# Optokoppleradapter_Spannungsmessung_V1_2.net
KiCad netlist of a schematic drawn in Altium Designer
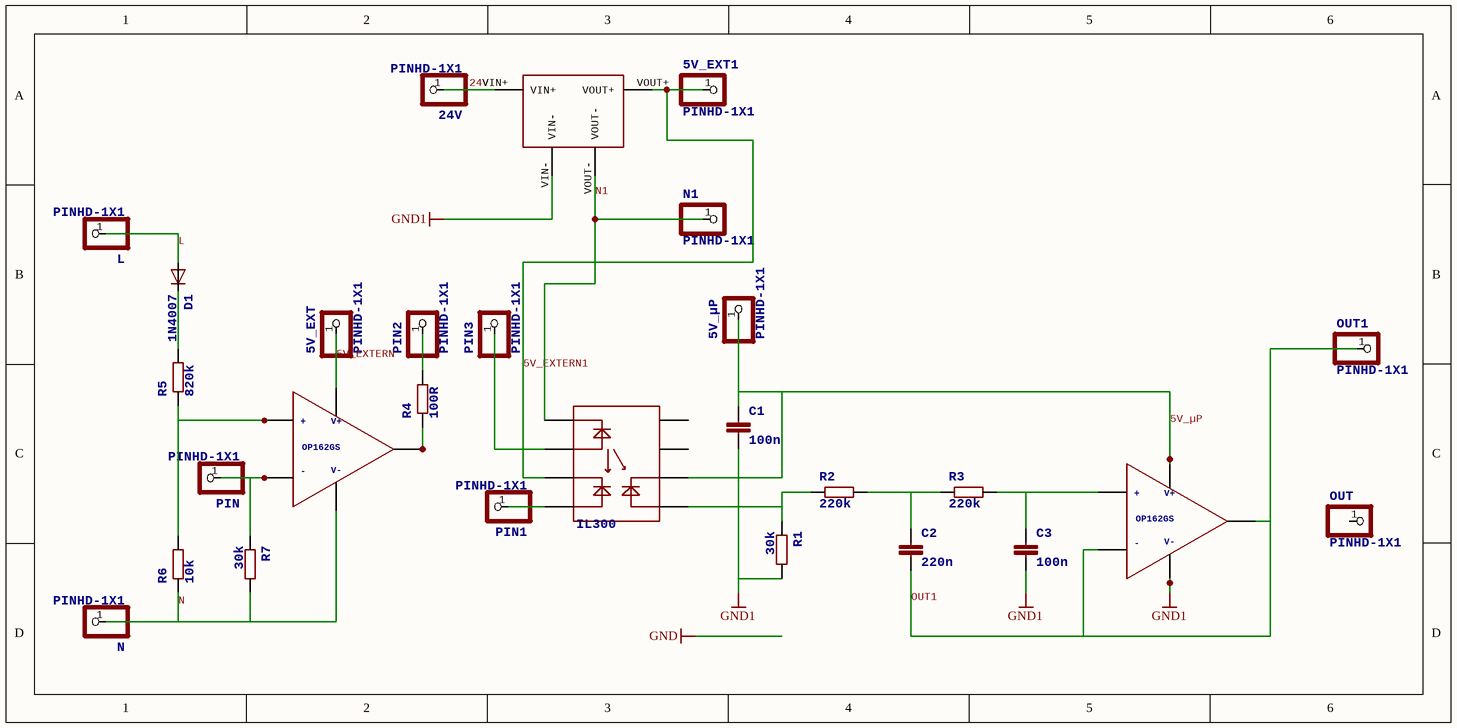
[diagram p0: Optokoppleradapter_Spannungsmessung_V1_2.SchDoc]

(export (version "E")
  (design (tool "Eeschema 10.0.6"))
  (components
    (comp (ref "5V_EXT")
      (value "PINHD-1X1")
      (footprint "1X01")
      (description "<b>PIN HEADER</b>")
      (libsource (lib "pinhead") (part "PINHD-1X1"))
    )
    (comp (ref "5V_EXT1")
      (value "PINHD-1X1")
      (footprint "1X01")
      (description "<b>PIN HEADER</b>")
      (libsource (lib "pinhead") (part "PINHD-1X1"))
    )
    (comp (ref "5V_µP")
      (value "PINHD-1X1")
      (footprint "1X01")
      (description "<b>PIN HEADER</b>")
      (libsource (lib "pinhead") (part "PINHD-1X1"))
    )
    (comp (ref "24V")
      (value "PINHD-1X1")
      (footprint "1X01")
      (description "<b>PIN HEADER</b>")
      (libsource (lib "pinhead") (part "PINHD-1X1"))
    )
    (comp (ref "C1")
      (value "100n")
      (footprint "C0805")
      (description "<B>CAPACITOR</B>, European symbol")
      (libsource (lib "resistor") (part "C-EUC0805"))
    )
    (comp (ref "C2")
      (value "220n")
      (footprint "C0805")
      (description "<B>CAPACITOR</B>, European symbol")
      (libsource (lib "resistor") (part "C-EUC0805"))
    )
    (comp (ref "C3")
      (value "100n")
      (footprint "C0805")
      (description "<B>CAPACITOR</B>, European symbol")
      (libsource (lib "resistor") (part "C-EUC0805"))
    )
    (comp (ref "D1")
      (value "1N4007")
      (footprint "DO35-7")
      (description "<B>DIODE</B><p>\nhigh speed (Philips)")
      (libsource (lib "diode") (part "1N4148DO35-7"))
    )
    (comp (ref "L")
      (value "PINHD-1X1")
      (footprint "1X01")
      (description "<b>PIN HEADER</b>")
      (libsource (lib "pinhead") (part "PINHD-1X1"))
    )
    (comp (ref "N")
      (value "PINHD-1X1")
      (footprint "1X01")
      (description "<b>PIN HEADER</b>")
      (libsource (lib "pinhead") (part "PINHD-1X1"))
    )
    (comp (ref "N1")
      (value "PINHD-1X1")
      (footprint "1X01")
      (description "<b>PIN HEADER</b>")
      (libsource (lib "pinhead") (part "PINHD-1X1"))
    )
    (comp (ref "OUT")
      (value "PINHD-1X1")
      (footprint "1X01")
      (description "<b>PIN HEADER</b>")
      (libsource (lib "pinhead") (part "PINHD-1X1"))
    )
    (comp (ref "OUT1")
      (value "PINHD-1X1")
      (footprint "1X01")
      (description "<b>PIN HEADER</b>")
      (libsource (lib "pinhead") (part "PINHD-1X1"))
    )
    (comp (ref "PIN")
      (value "PINHD-1X1")
      (footprint "1X01")
      (description "<b>PIN HEADER</b>")
      (libsource (lib "pinhead") (part "PINHD-1X1"))
    )
    (comp (ref "PIN1")
      (value "PINHD-1X1")
      (footprint "1X01")
      (description "<b>PIN HEADER</b>")
      (libsource (lib "pinhead") (part "PINHD-1X1"))
    )
    (comp (ref "PIN2")
      (value "PINHD-1X1")
      (footprint "1X01")
      (description "<b>PIN HEADER</b>")
      (libsource (lib "pinhead") (part "PINHD-1X1"))
    )
    (comp (ref "PIN3")
      (value "PINHD-1X1")
      (footprint "1X01")
      (description "<b>PIN HEADER</b>")
      (libsource (lib "pinhead") (part "PINHD-1X1"))
    )
    (comp (ref "R1")
      (value "30k")
      (footprint "R0805")
      (description "<B>RESISTOR</B>, European symbol")
      (libsource (lib "resistor") (part "R-EU_R0805"))
    )
    (comp (ref "R2")
      (value "220k")
      (footprint "R0805")
      (description "<B>RESISTOR</B>, European symbol")
      (libsource (lib "resistor") (part "R-EU_R0805"))
    )
    (comp (ref "R3")
      (value "220k")
      (footprint "R0805")
      (description "<B>RESISTOR</B>, European symbol")
      (libsource (lib "resistor") (part "R-EU_R0805"))
    )
    (comp (ref "R4")
      (value "100R")
      (footprint "R0805")
      (description "<B>RESISTOR</B>, European symbol")
      (libsource (lib "resistor") (part "R-EU_R0805"))
    )
    (comp (ref "R5")
      (value "820k")
      (footprint "0207/7")
      (description "<B>RESISTOR</B>, European symbol")
      (libsource (lib "resistor") (part "R-EU_0207/7"))
    )
    (comp (ref "R6")
      (value "10k")
      (footprint "0207/7")
      (description "<B>RESISTOR</B>, European symbol")
      (libsource (lib "resistor") (part "R-EU_0207/7"))
    )
    (comp (ref "R7")
      (value "30k")
      (footprint "0207/7")
      (description "<B>RESISTOR</B>, European symbol")
      (libsource (lib "resistor") (part "R-EU_0207/7"))
    )
    (comp (ref "U$1")
      (value "IL300")
      (footprint "DIP8")
      (fields (field (name "IL300") "IL300"))
      (libsource (lib "ADS") (part "IL300"))
    )
    (comp (ref "U$2")
      (value "OP162GS")
      (footprint "SOIC_N")
      (fields
        (field (name "+") "+")
        (field (name "-") "-")
        (field (name "OP162GS") "OP162GS")
        (field (name "V+") "V+")
        (field (name "V-") "V-")
      )
      (libsource (lib "ADS") (part "OP162GS"))
    )
    (comp (ref "U$3")
      (value "OP162GS")
      (footprint "SOIC_N")
      (fields
        (field (name "+") "+")
        (field (name "-") "-")
        (field (name "OP162GS") "OP162GS")
        (field (name "V+") "V+")
        (field (name "V-") "V-")
      )
      (libsource (lib "ADS") (part "OP162GS"))
    )
    (comp (ref "U$4")
      (value "RECOM_RO-2405S")
      (footprint "4PIN_SIP")
      (libsource (lib "ADS") (part "RECOM_RO-2405S"))
    )
  )
  (nets
    (net (code "1") (name "/5V_EXTERN") (class "Default")
      (node (ref "5V_EXT") (pin "1") (pinfunction "1_1") (pintype "passive"))
      (node (ref "U$2") (pin "P$7") (pinfunction "V+_P$7") (pintype "passive"))
    )
    (net (code "2") (name "/5V_EXTERN1") (class "Default")
      (node (ref "5V_EXT1") (pin "1") (pinfunction "1_1") (pintype "passive"))
      (node (ref "U$1") (pin "P$3") (pinfunction "P$3_P$3") (pintype "passive"))
      (node (ref "U$4") (pin "VOUT+") (pinfunction "VOUT+_VOUT+") (pintype "passive"))
    )
    (net (code "3") (name "/5V_µP") (class "Default")
      (node (ref "5V_µP") (pin "1") (pinfunction "1_1") (pintype "passive"))
      (node (ref "C1") (pin "1") (pinfunction "1_1") (pintype "passive"))
      (node (ref "U$1") (pin "P$6") (pinfunction "P$6_P$6") (pintype "passive"))
      (node (ref "U$3") (pin "P$7") (pinfunction "V+_P$7") (pintype "passive"))
    )
    (net (code "4") (name "/24V") (class "Default")
      (node (ref "24V") (pin "1") (pinfunction "1_1") (pintype "passive"))
      (node (ref "U$4") (pin "VIN+") (pinfunction "VIN+_VIN+") (pintype "passive"))
    )
    (net (code "5") (name "/L") (class "Default")
      (node (ref "D1") (pin "A") (pinfunction "A_A") (pintype "passive"))
      (node (ref "L") (pin "1") (pinfunction "1_1") (pintype "passive"))
    )
    (net (code "6") (name "/N") (class "Default")
      (node (ref "N") (pin "1") (pinfunction "1_1") (pintype "passive"))
      (node (ref "R6") (pin "1") (pinfunction "1_1") (pintype "passive"))
      (node (ref "R7") (pin "2") (pinfunction "2_2") (pintype "passive"))
      (node (ref "U$2") (pin "P$4") (pinfunction "V-_P$4") (pintype "passive"))
    )
    (net (code "7") (name "/N1") (class "Default")
      (node (ref "N1") (pin "1") (pinfunction "1_1") (pintype "passive"))
      (node (ref "U$1") (pin "P$1") (pinfunction "P$1_P$1") (pintype "passive"))
      (node (ref "U$4") (pin "VOUT-") (pinfunction "VOUT-_VOUT-") (pintype "passive"))
    )
    (net (code "8") (name "/OUT1") (class "Default")
      (node (ref "C2") (pin "2") (pinfunction "2_2") (pintype "passive"))
      (node (ref "OUT1") (pin "1") (pinfunction "1_1") (pintype "passive"))
      (node (ref "U$3") (pin "P$2") (pinfunction "-_P$2") (pintype "passive"))
      (node (ref "U$3") (pin "P$6") (pinfunction "OUT_P$6") (pintype "passive"))
    )
    (net (code "10") (name "GND1") (class "Default")
      (node (ref "C1") (pin "2") (pinfunction "2_2") (pintype "passive"))
      (node (ref "C3") (pin "2") (pinfunction "2_2") (pintype "passive"))
      (node (ref "R1") (pin "2") (pinfunction "2_2") (pintype "passive"))
      (node (ref "U$3") (pin "P$4") (pinfunction "V-_P$4") (pintype "passive"))
      (node (ref "U$4") (pin "VIN-") (pinfunction "VIN-_VIN-") (pintype "passive"))
    )
    (net (code "11") (name "Net-(C2-Pad1)") (class "Default")
      (node (ref "C2") (pin "1") (pinfunction "1_1") (pintype "passive"))
      (node (ref "R2") (pin "2") (pinfunction "2_2") (pintype "passive"))
      (node (ref "R3") (pin "1") (pinfunction "1_1") (pintype "passive"))
    )
    (net (code "12") (name "Net-(D1-PadC)") (class "Default")
      (node (ref "D1") (pin "C") (pinfunction "C_C") (pintype "passive"))
      (node (ref "R5") (pin "2") (pinfunction "2_2") (pintype "passive"))
    )
    (net (code "13") (name "Net-(PIN1-Pad1)") (class "Default")
      (node (ref "PIN1") (pin "1") (pinfunction "1_1") (pintype "passive"))
      (node (ref "U$1") (pin "P$4") (pinfunction "P$4_P$4") (pintype "passive"))
    )
    (net (code "14") (name "Net-(PIN2-Pad1)") (class "Default")
      (node (ref "PIN2") (pin "1") (pinfunction "1_1") (pintype "passive"))
      (node (ref "R4") (pin "2") (pinfunction "2_2") (pintype "passive"))
    )
    (net (code "15") (name "Net-(PIN3-Pad1)") (class "Default")
      (node (ref "PIN3") (pin "1") (pinfunction "1_1") (pintype "passive"))
      (node (ref "U$1") (pin "P$2") (pinfunction "P$2_P$2") (pintype "passive"))
    )
    (net (code "16") (name "Net-(R1-Pad1)") (class "Default")
      (node (ref "R1") (pin "1") (pinfunction "1_1") (pintype "passive"))
      (node (ref "R2") (pin "1") (pinfunction "1_1") (pintype "passive"))
      (node (ref "U$1") (pin "P$5") (pinfunction "P$5_P$5") (pintype "passive"))
    )
    (net (code "17") (name "Net-(U$2-+)") (class "Default")
      (node (ref "R5") (pin "1") (pinfunction "1_1") (pintype "passive"))
      (node (ref "R6") (pin "2") (pinfunction "2_2") (pintype "passive"))
      (node (ref "U$2") (pin "P$3") (pinfunction "+_P$3") (pintype "passive"))
    )
    (net (code "18") (name "Net-(U$2--)") (class "Default")
      (node (ref "PIN") (pin "1") (pinfunction "1_1") (pintype "passive"))
      (node (ref "R7") (pin "1") (pinfunction "1_1") (pintype "passive"))
      (node (ref "U$2") (pin "P$2") (pinfunction "-_P$2") (pintype "passive"))
    )
    (net (code "19") (name "Net-(U$2-OUT)") (class "Default")
      (node (ref "R4") (pin "1") (pinfunction "1_1") (pintype "passive"))
      (node (ref "U$2") (pin "P$6") (pinfunction "OUT_P$6") (pintype "passive"))
    )
    (net (code "20") (name "Net-(U$3-+)") (class "Default")
      (node (ref "C3") (pin "1") (pinfunction "1_1") (pintype "passive"))
      (node (ref "R3") (pin "2") (pinfunction "2_2") (pintype "passive"))
      (node (ref "U$3") (pin "P$3") (pinfunction "+_P$3") (pintype "passive"))
    )
    (net (code "21") (name "unconnected-(OUT-Pad1)") (class "Default")
      (node (ref "OUT") (pin "1") (pinfunction "1_1") (pintype "passive"))
    )
    (net (code "22") (name "unconnected-(U$1-PadP$7)") (class "Default")
      (node (ref "U$1") (pin "P$7") (pinfunction "P$7_P$7") (pintype "passive"))
    )
    (net (code "23") (name "unconnected-(U$1-PadP$8)") (class "Default")
      (node (ref "U$1") (pin "P$8") (pinfunction "P$8_P$8") (pintype "passive"))
    )
  )
)
